# 06_POWER-INPUT.net
KiCad netlist of a schematic drawn in Altium Designer
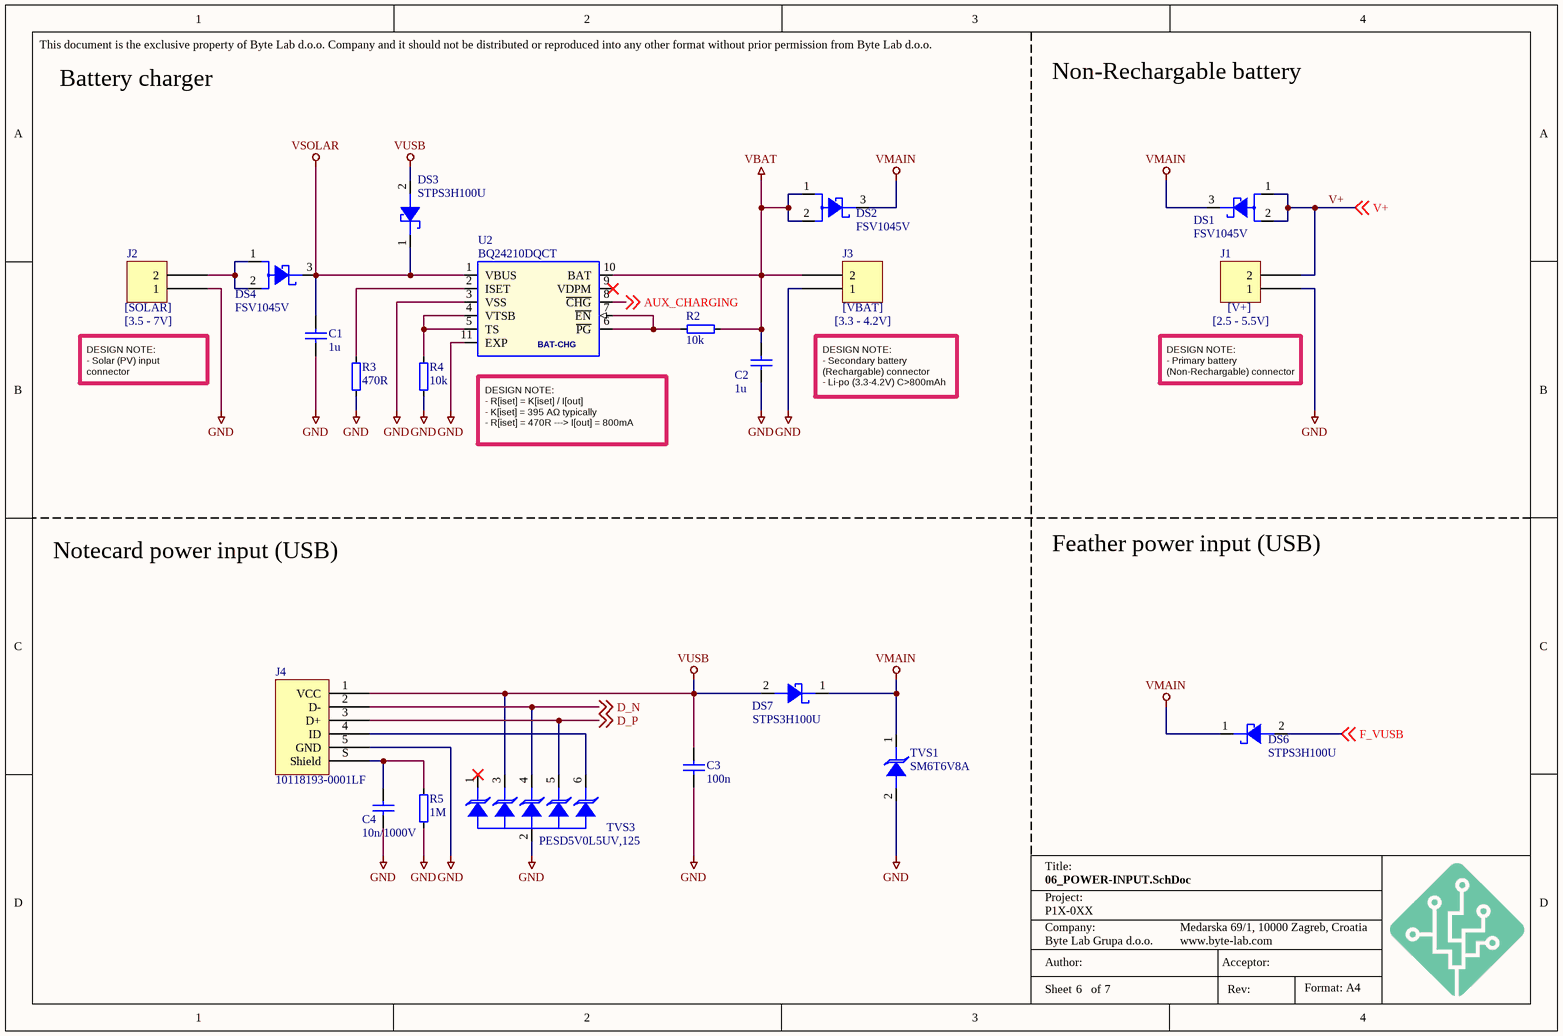
[diagram p0: 06_POWER-INPUT.SchDoc]

(export (version "E")
  (design (tool "Eeschema 10.0.6"))
  (components
    (comp (ref "C1")
      (value "1u")
      (footprint "C-0603")
      (description "Capacitor ceramic 1u ±10% X5R 25V")
      (fields
        (field (name "MANUFACTURER") "Yageo")
        (field (name "BL PART NUMBER") "2006-223")
        (field (name "DRAWN_BY") "Hamin")
        (field (name "CHECKED_BY") "Golubic")
      )
      (libsource (lib "BL_Passive") (part "C0603-1u-25V-X5R"))
    )
    (comp (ref "C2")
      (value "1u")
      (footprint "C-0603")
      (description "Capacitor ceramic 1u ±10% X5R 25V")
      (fields
        (field (name "MANUFACTURER") "Yageo")
        (field (name "BL PART NUMBER") "2006-223")
        (field (name "DRAWN_BY") "Hamin")
        (field (name "CHECKED_BY") "Golubic")
      )
      (libsource (lib "BL_Passive") (part "C0603-1u-25V-X5R"))
    )
    (comp (ref "C3")
      (value "100n")
      (footprint "C-0402")
      (description "Capacitor ceramic 100n ±10% X7R 16V 0402")
      (fields
        (field (name "BL PART NUMBER") "2000-908")
        (field (name "DRAWN_BY") "Puskar")
        (field (name "CHECKED_BY") "Dodig")
      )
      (libsource (lib "BL_Passive") (part "C0402-100n-16V-X7R"))
    )
    (comp (ref "C4")
      (value "10n/1000V")
      (footprint "C-1206")
      (description "Capacitor ceramic 10n ±10% X7R 1000V 1206")
      (fields
        (field (name "MANUFACTURER") "YAGEO")
        (field (name "BL PART NUMBER") "2007-449")
        (field (name "DRAWN_BY") "Hamin")
        (field (name "CHECKED_BY") "*")
      )
      (libsource (lib "BL_Passive") (part "C1206-10n-1000V-X7R - CS1206KKX7RCBB103"))
    )
    (comp (ref "DS1")
      (value "FSV1045V")
      (footprint "TO277-3")
      (description "DIODO SCHOTTKY 10A 45V FSV1045V TO277-3 SMT")
      (fields
        (field (name "BL PART NUMBER") "2007-712")
        (field (name "MANUFACTURER") "onsemi")
        (field (name "DRAWN_BY") "Blues Wireless")
      )
      (libsource (lib "n21-p2") (part "SCHOTTKY - FSV1045V - 10A/45V"))
    )
    (comp (ref "DS2")
      (value "FSV1045V")
      (footprint "TO277-3")
      (description "DIODO SCHOTTKY 10A 45V FSV1045V TO277-3 SMT")
      (fields
        (field (name "BL PART NUMBER") "2007-712")
        (field (name "MANUFACTURER") "onsemi")
        (field (name "DRAWN_BY") "Blues Wireless")
      )
      (libsource (lib "n21-p2") (part "SCHOTTKY - FSV1045V - 10A/45V"))
    )
    (comp (ref "DS3")
      (value "STPS3H100U")
      (footprint "SMB")
      (description "DIODO SCHOTTKY 3A 100V STPS3H100U SMB SMT")
      (fields
        (field (name "MANUFACTURER") "STMicroelectronics")
        (field (name "BL PART NUMBER") "2007-711")
        (field (name "DRAWN_BY") "Blues Wireless")
      )
      (libsource (lib "n21-p2") (part "SCHOTTKY-STPS3H100U - 3A/100V"))
    )
    (comp (ref "DS4")
      (value "FSV1045V")
      (footprint "TO277-3")
      (description "DIODO SCHOTTKY 10A 45V FSV1045V TO277-3 SMT")
      (fields
        (field (name "BL PART NUMBER") "2007-712")
        (field (name "MANUFACTURER") "onsemi")
        (field (name "DRAWN_BY") "Blues Wireless")
      )
      (libsource (lib "n21-p2") (part "SCHOTTKY - FSV1045V - 10A/45V"))
    )
    (comp (ref "DS6")
      (value "STPS3H100U")
      (footprint "SMB")
      (description "DIODO SCHOTTKY 3A 100V STPS3H100U SMB SMT")
      (fields
        (field (name "MANUFACTURER") "STMicroelectronics")
        (field (name "BL PART NUMBER") "2007-711")
        (field (name "DRAWN_BY") "Blues Wireless")
      )
      (libsource (lib "n21-p2") (part "SCHOTTKY-STPS3H100U - 3A/100V"))
    )
    (comp (ref "DS7")
      (value "STPS3H100U")
      (footprint "SMB")
      (description "DIODO SCHOTTKY 3A 100V STPS3H100U SMB SMT")
      (fields
        (field (name "MANUFACTURER") "STMicroelectronics")
        (field (name "BL PART NUMBER") "2007-711")
        (field (name "DRAWN_BY") "Blues Wireless")
      )
      (libsource (lib "n21-p2") (part "SCHOTTKY-STPS3H100U - 3A/100V"))
    )
    (comp (ref "J1")
      (value "S2BPHSM4TBLFSN")
      (footprint "JST S2B-PH-SM4-TB")
      (description "PH SMT SIDE ENTRY HDR 2W")
      (fields
        (field (name "MANUFACTURER") "JST")
        (field (name "MANUFACTURER PART NUMBER") "S2B-PH-SM4-K-TB (LF)(SN)")
        (field (name "DRAWN_BY") "Blues Wireless")
      )
      (libsource (lib "n21-p2") (part "S2BPHSM4TBLFSN"))
    )
    (comp (ref "J2")
      (value "S2BPHSM4TBLFSN")
      (footprint "JST S2B-PH-SM4-TB")
      (description "PH SMT SIDE ENTRY HDR 2W")
      (fields
        (field (name "MANUFACTURER") "JST")
        (field (name "MANUFACTURER PART NUMBER") "S2B-PH-SM4-K-TB (LF)(SN)")
        (field (name "DRAWN_BY") "Blues Wireless")
      )
      (libsource (lib "n21-p2") (part "S2BPHSM4TBLFSN"))
    )
    (comp (ref "J3")
      (value "S2BPHSM4TBLFSN")
      (footprint "JST S2B-PH-SM4-TB")
      (description "PH SMT SIDE ENTRY HDR 2W")
      (fields
        (field (name "MANUFACTURER") "JST")
        (field (name "MANUFACTURER PART NUMBER") "S2B-PH-SM4-K-TB (LF)(SN)")
        (field (name "DRAWN_BY") "Blues Wireless")
      )
      (libsource (lib "") (part "S2BPHSM4TBLFSN_1"))
    )
    (comp (ref "J4")
      (value "10118193-0001LF")
      (footprint "FCI USB 10118193-0001LF")
      (description "CONN RCPT USB2.0 MICRO B SMD R/A")
      (fields (field (name "MANUFACTURER") "Amphenol ICC (FCI)") (field (name "BL PART NUMBER") "2007-454"))
      (libsource (lib "n21-p2") (part "USB 2.0 Type B Micro"))
    )
    (comp (ref "R2")
      (value "10k")
      (footprint "R-0402")
      (description "Resistor 10k ±1% 0402")
      (fields
        (field (name "BL PART NUMBER") "2000-729")
        (field (name "CHECKED_BY") "Dodig")
        (field (name "DRAWN_BY") "Puskar")
      )
      (libsource (lib "BL_Passive") (part "R0402-10k-1"))
    )
    (comp (ref "R3")
      (value "470R")
      (footprint "R-0402")
      (description "Resistor 470R ±1% 0402")
      (fields
        (field (name "BL PART NUMBER") "2001-420")
        (field (name "CHECKED_BY") "*")
        (field (name "DRAWN_BY") "Hamin")
      )
      (libsource (lib "BL_Passive") (part "R0402-470R-1"))
    )
    (comp (ref "R4")
      (value "10k")
      (footprint "R-0402")
      (description "Resistor 10k ±1% 0402")
      (fields
        (field (name "BL PART NUMBER") "2000-729")
        (field (name "CHECKED_BY") "Dodig")
        (field (name "DRAWN_BY") "Puskar")
      )
      (libsource (lib "BL_Passive") (part "R0402-10k-1"))
    )
    (comp (ref "R5")
      (value "1M")
      (footprint "R-1206")
      (description "Resistor 1M ±1% 1206")
      (fields
        (field (name "BL PART NUMBER") "2001-438")
        (field (name "CHECKED_BY") "Golubic")
        (field (name "DRAWN_BY") "Zvonc")
      )
      (libsource (lib "BL_Passive") (part "R1206-1M-1"))
    )
    (comp (ref "TVS1")
      (value "SM6T6V8A")
      (footprint "SMB")
      (description "DIODO TVS TRANSIL UNIDIR. 600W 6.8V SM6T6V8A SMB SMT")
      (fields
        (field (name "BL PART NUMBER") "2007-453")
        (field (name "MANUFACTURER") "STMicroelectronics")
        (field (name "DRAWN_BY") "Blues Wireless")
      )
      (libsource (lib "n21-p2") (part "TVS-UNI - SM6T6V8A - 6.8V/600W"))
    )
    (comp (ref "TVS3")
      (value "PESD5V0L5UV,125")
      (footprint "SOT666")
      (description "PESD Series 25 W 5 V Uni-Directional Fivefold ESD Protection Diode Array SOT-666")
      (fields
        (field (name "MANUFACTURER") "Nexperia")
        (field (name "BL PART NUMBER") "2007-452")
        (field (name "DRAWN_BY") "Blues Wireless")
      )
      (libsource (lib "n21-p2") (part "PESD5V0L5UV,125"))
    )
    (comp (ref "U2")
      (value "BQ24210DQCT")
      (footprint "WSON10-EXP")
      (description "INTEGRATO BQ24210DQCT WSON10 TEXAS SMT")
      (fields
        (field (name "BL PART NUMBER") "2005-527")
        (field (name "MANUFACTURER") "Texas Instruments")
        (field (name "DRAWN_BY") "Blues Wireless")
      )
      (libsource (lib "n21-p2") (part "BAT-CHARGE - BQ24210DQCT"))
    )
  )
  (nets
    (net (code "1") (name "AUX_CHARGING") (class "Default")
      (node (ref "U2") (pin "8") (pinfunction "~{CHG}_8") (pintype "open_collector"))
    )
    (net (code "2") (name "D_N") (class "Default")
      (node (ref "J4") (pin "2") (pinfunction "D-_2") (pintype "passive"))
      (node (ref "TVS3") (pin "4") (pinfunction "C4_4") (pintype "passive"))
    )
    (net (code "3") (name "D_P") (class "Default")
      (node (ref "J4") (pin "3") (pinfunction "D+_3") (pintype "passive"))
      (node (ref "TVS3") (pin "5") (pinfunction "A5_5") (pintype "passive"))
    )
    (net (code "4") (name "F_VUSB") (class "Default")
      (node (ref "DS6") (pin "2") (pinfunction "A_2") (pintype "passive"))
    )
    (net (code "5") (name "GND") (class "Default")
      (node (ref "C1") (pin "1") (pinfunction "1_1") (pintype "passive"))
      (node (ref "C2") (pin "1") (pinfunction "1_1") (pintype "passive"))
      (node (ref "C3") (pin "2") (pinfunction "2_2") (pintype "passive"))
      (node (ref "C4") (pin "2") (pinfunction "2_2") (pintype "passive"))
      (node (ref "J1") (pin "1") (pinfunction "1_1") (pintype "passive"))
      (node (ref "J2") (pin "1") (pinfunction "1_1") (pintype "passive"))
      (node (ref "J3") (pin "1") (pinfunction "1_1") (pintype "passive"))
      (node (ref "J4") (pin "5") (pinfunction "GND_5") (pintype "passive"))
      (node (ref "R3") (pin "1") (pintype "passive"))
      (node (ref "R4") (pin "1") (pintype "passive"))
      (node (ref "R5") (pin "2") (pintype "passive"))
      (node (ref "TVS1") (pin "2") (pinfunction "A_2") (pintype "passive"))
      (node (ref "TVS3") (pin "2") (pinfunction "A2_2") (pintype "passive"))
      (node (ref "U2") (pin "11") (pinfunction "EXP_11") (pintype "passive"))
      (node (ref "U2") (pin "3") (pinfunction "VSS_3") (pintype "power_in"))
    )
    (net (code "6") (name "Net-(DS4-A1)") (class "Default")
      (node (ref "DS4") (pin "1") (pinfunction "A1_1") (pintype "passive"))
      (node (ref "DS4") (pin "2") (pinfunction "A2_2") (pintype "passive"))
      (node (ref "J2") (pin "2") (pinfunction "2_2") (pintype "passive"))
    )
    (net (code "7") (name "Net-(J4-ID)") (class "Default")
      (node (ref "J4") (pin "4") (pinfunction "ID_4") (pintype "passive"))
      (node (ref "TVS3") (pin "6") (pinfunction "C6_6") (pintype "passive"))
    )
    (net (code "8") (name "Net-(J4-Shield)") (class "Default")
      (node (ref "C4") (pin "1") (pinfunction "1_1") (pintype "passive"))
      (node (ref "J4") (pin "S") (pinfunction "Shield_S") (pintype "passive"))
      (node (ref "R5") (pin "1") (pintype "passive"))
    )
    (net (code "9") (name "Net-(U2-ISET)") (class "Default")
      (node (ref "R3") (pin "2") (pintype "passive"))
      (node (ref "U2") (pin "2") (pinfunction "ISET_2") (pintype "passive"))
    )
    (net (code "10") (name "Net-(U2-TS)") (class "Default")
      (node (ref "R4") (pin "2") (pintype "passive"))
      (node (ref "U2") (pin "4") (pinfunction "VTSB_4") (pintype "passive"))
      (node (ref "U2") (pin "5") (pinfunction "TS_5") (pintype "passive"))
    )
    (net (code "11") (name "Net-(U2-~{EN})") (class "Default")
      (node (ref "R2") (pin "1") (pintype "passive"))
      (node (ref "U2") (pin "6") (pinfunction "~{PG}_6") (pintype "open_collector"))
      (node (ref "U2") (pin "7") (pinfunction "~{EN}_7") (pintype "input"))
    )
    (net (code "12") (name "V+") (class "Default")
      (node (ref "DS1") (pin "1") (pinfunction "A1_1") (pintype "passive"))
      (node (ref "DS1") (pin "2") (pinfunction "A2_2") (pintype "passive"))
      (node (ref "J1") (pin "2") (pinfunction "2_2") (pintype "passive"))
    )
    (net (code "13") (name "VBAT") (class "Default")
      (node (ref "C2") (pin "2") (pinfunction "2_2") (pintype "passive"))
      (node (ref "DS2") (pin "1") (pinfunction "A1_1") (pintype "passive"))
      (node (ref "DS2") (pin "2") (pinfunction "A2_2") (pintype "passive"))
      (node (ref "J3") (pin "2") (pinfunction "2_2") (pintype "passive"))
      (node (ref "R2") (pin "2") (pintype "passive"))
      (node (ref "U2") (pin "10") (pinfunction "BAT_10") (pintype "power_in"))
    )
    (net (code "14") (name "VMAIN") (class "Default")
      (node (ref "DS1") (pin "3") (pinfunction "C_3") (pintype "passive"))
      (node (ref "DS2") (pin "3") (pinfunction "C_3") (pintype "passive"))
      (node (ref "DS6") (pin "1") (pinfunction "C_1") (pintype "passive"))
      (node (ref "DS7") (pin "1") (pinfunction "C_1") (pintype "passive"))
      (node (ref "TVS1") (pin "1") (pinfunction "C_1") (pintype "passive"))
    )
    (net (code "15") (name "VSOLAR") (class "Default")
      (node (ref "C1") (pin "2") (pinfunction "2_2") (pintype "passive"))
      (node (ref "DS3") (pin "1") (pinfunction "C_1") (pintype "passive"))
      (node (ref "DS4") (pin "3") (pinfunction "C_3") (pintype "passive"))
      (node (ref "U2") (pin "1") (pinfunction "VBUS_1") (pintype "power_in"))
    )
    (net (code "16") (name "VUSB") (class "Default")
      (node (ref "C3") (pin "1") (pinfunction "1_1") (pintype "passive"))
      (node (ref "DS3") (pin "2") (pinfunction "A_2") (pintype "passive"))
      (node (ref "DS7") (pin "2") (pinfunction "A_2") (pintype "passive"))
      (node (ref "J4") (pin "1") (pinfunction "VCC_1") (pintype "passive"))
      (node (ref "TVS3") (pin "3") (pinfunction "C3_3") (pintype "passive"))
    )
    (net (code "17") (name "unconnected-(TVS3-C1-Pad1)") (class "Default")
      (node (ref "TVS3") (pin "1") (pinfunction "C1_1") (pintype "passive+no_connect"))
    )
    (net (code "18") (name "unconnected-(U2-VDPM-Pad9)") (class "Default")
      (node (ref "U2") (pin "9") (pinfunction "VDPM_9") (pintype "passive+no_connect"))
    )
  )
)
